# SparkFun_GPS_ZED-F9K.net
KiCad netlist of a schematic drawn in EAGLE
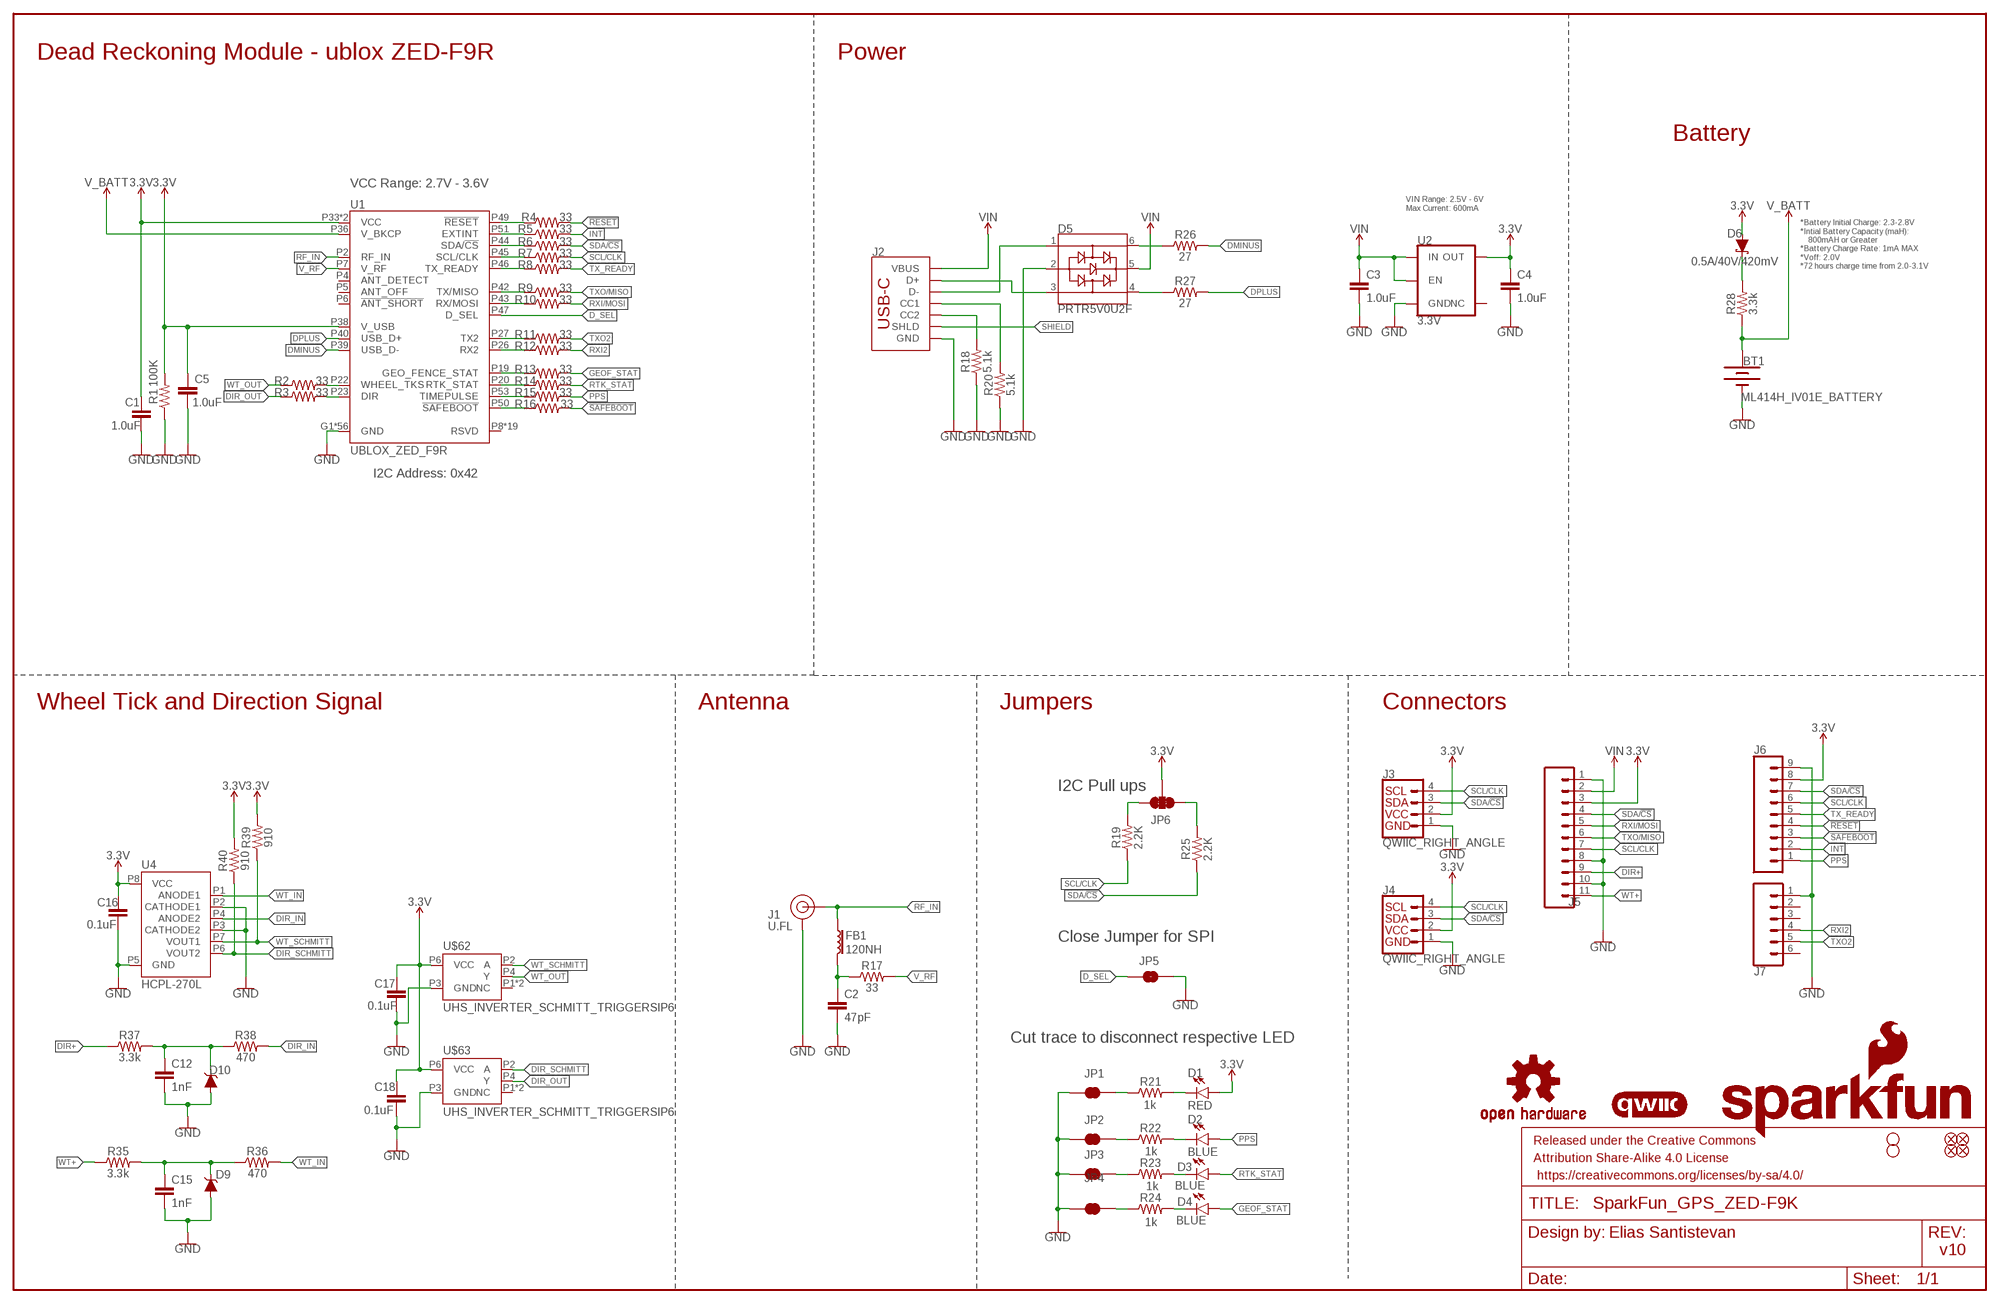
[diagram p0: schematic, sheet 1]

(export (version "E")
  (design (tool "Eeschema 10.0.6"))
  (components
    (comp (ref "$1_36_$_2020-02-13_17-32-45")
      (value "STAND-OFFTIGHT")
      (footprint "eagle-import:STAND-OFF-TIGHT")
      (libsource (lib "eagle-import") (part "STAND-OFFTIGHT"))
    )
    (comp (ref "BT1")
      (value "ML414H_IV01E_BATTERY")
      (footprint "eagle-import:ML414H_IV01E")
      (libsource (lib "eagle-import") (part "ML414H_IV01E_BATTERY"))
    )
    (comp (ref "C1")
      (value "1.0uF")
      (footprint "eagle-import:0603")
      (libsource (lib "eagle-import") (part "1.0UF-0603-16V-10%-X7R"))
    )
    (comp (ref "C2")
      (value "47pF")
      (footprint "eagle-import:0402")
      (libsource (lib "eagle-import") (part "47PF-0402-25V-5%-X7R"))
    )
    (comp (ref "C3")
      (value "1.0uF")
      (footprint "eagle-import:0603")
      (libsource (lib "eagle-import") (part "1.0UF-0603-16V-10%-X7R"))
    )
    (comp (ref "C4")
      (value "1.0uF")
      (footprint "eagle-import:0603")
      (libsource (lib "eagle-import") (part "1.0UF-0603-16V-10%-X7R"))
    )
    (comp (ref "C5")
      (value "1.0uF")
      (footprint "eagle-import:0603")
      (libsource (lib "eagle-import") (part "1.0UF-0603-16V-10%-X7R"))
    )
    (comp (ref "C12")
      (value "1nF")
      (footprint "eagle-import:0402")
      (libsource (lib "eagle-import") (part "1.0NF/1000PF-0402-25V-10%-X7R"))
    )
    (comp (ref "C15")
      (value "1nF")
      (footprint "eagle-import:0402")
      (libsource (lib "eagle-import") (part "1.0NF/1000PF-0402-25V-10%-X7R"))
    )
    (comp (ref "C16")
      (value "0.1uF")
      (footprint "eagle-import:0402")
      (libsource (lib "eagle-import") (part "0.1UF-0402-6.3V-10%-X7R"))
    )
    (comp (ref "C17")
      (value "0.1uF")
      (footprint "eagle-import:0402")
      (libsource (lib "eagle-import") (part "0.1UF-0402-6.3V-10%-X7R"))
    )
    (comp (ref "C18")
      (value "0.1uF")
      (footprint "eagle-import:0402")
      (libsource (lib "eagle-import") (part "0.1UF-0402-6.3V-10%-X7R"))
    )
    (comp (ref "D1")
      (value "RED")
      (footprint "eagle-import:LED-0603")
      (libsource (lib "eagle-import") (part "LED-RED0603"))
    )
    (comp (ref "D2")
      (value "BLUE")
      (footprint "eagle-import:LED-0603")
      (libsource (lib "eagle-import") (part "LED-BLUE0603"))
    )
    (comp (ref "D3")
      (value "BLUE")
      (footprint "eagle-import:LED-0603")
      (libsource (lib "eagle-import") (part "LED-BLUE0603"))
    )
    (comp (ref "D4")
      (value "BLUE")
      (footprint "eagle-import:LED-0603")
      (libsource (lib "eagle-import") (part "LED-BLUE0603"))
    )
    (comp (ref "D5")
      (value "PRTR5V0U2F")
      (footprint "eagle-import:SOT886")
      (libsource (lib "eagle-import") (part "PRTR5V0U2F"))
    )
    (comp (ref "D6")
      (value "0.5A/40V/420mV")
      (footprint "eagle-import:SOD-323")
      (libsource (lib "eagle-import") (part "DIODE-SCHOTTKY-PMEG4005EJ"))
    )
    (comp (ref "D9")
      (value "0.5A/40V/420mV")
      (footprint "eagle-import:SOT23_BZX")
      (libsource (lib "eagle-import") (part "BZX84_DIODE"))
    )
    (comp (ref "D10")
      (value "0.5A/40V/420mV")
      (footprint "eagle-import:SOT23_BZX")
      (libsource (lib "eagle-import") (part "BZX84_DIODE"))
    )
    (comp (ref "FB1")
      (value "120NH")
      (footprint "eagle-import:0402_MURATA")
      (libsource (lib "eagle-import") (part "FERRITE_BEAD_GNSS"))
    )
    (comp (ref "FD1")
      (value "FIDUCIALUFIDUCIAL")
      (footprint "eagle-import:FIDUCIAL-MICRO")
      (libsource (lib "eagle-import") (part "FIDUCIALUFIDUCIAL"))
    )
    (comp (ref "FD2")
      (value "FIDUCIALUFIDUCIAL")
      (footprint "eagle-import:FIDUCIAL-MICRO")
      (libsource (lib "eagle-import") (part "FIDUCIALUFIDUCIAL"))
    )
    (comp (ref "FD3")
      (value "FIDUCIALUFIDUCIAL")
      (footprint "eagle-import:FIDUCIAL-MICRO")
      (libsource (lib "eagle-import") (part "FIDUCIALUFIDUCIAL"))
    )
    (comp (ref "FD4")
      (value "FIDUCIALUFIDUCIAL")
      (footprint "eagle-import:FIDUCIAL-MICRO")
      (libsource (lib "eagle-import") (part "FIDUCIALUFIDUCIAL"))
    )
    (comp (ref "FRAME1")
      (value "FRAME-LEDGER")
      (footprint "eagle-import:CREATIVE_COMMONS")
      (libsource (lib "eagle-import") (part "FRAME-LEDGER"))
    )
    (comp (ref "H2")
      (value "STAND-OFFTIGHT")
      (footprint "eagle-import:STAND-OFF-TIGHT")
      (libsource (lib "eagle-import") (part "STAND-OFFTIGHT"))
    )
    (comp (ref "J1")
      (value "U.FL")
      (footprint "eagle-import:U.FL")
      (libsource (lib "eagle-import") (part "U.FL2PIN"))
    )
    (comp (ref "J2")
      (value "USB_C_2-LAYER_PADS")
      (footprint "eagle-import:USB-C-16P-2LAYER-PADS")
      (libsource (lib "eagle-import") (part "USB_C_2-LAYER_PADS"))
    )
    (comp (ref "J3")
      (value "QWIIC_RIGHT_ANGLE")
      (footprint "eagle-import:JST04_1MM_RA")
      (libsource (lib "eagle-import") (part "QWIIC_CONNECTORJS-1MM"))
    )
    (comp (ref "J4")
      (value "QWIIC_RIGHT_ANGLE")
      (footprint "eagle-import:JST04_1MM_RA")
      (libsource (lib "eagle-import") (part "QWIIC_CONNECTORJS-1MM"))
    )
    (comp (ref "J5")
      (value "CONN_111X11_NO_SILK")
      (footprint "eagle-import:1X11_NO_SILK")
      (libsource (lib "eagle-import") (part "CONN_111X11_NO_SILK"))
    )
    (comp (ref "J6")
      (value "CONN_09NO_SILK")
      (footprint "eagle-import:1X09_NO_SILK")
      (libsource (lib "eagle-import") (part "CONN_09NO_SILK"))
    )
    (comp (ref "J7")
      (value "CONN_06NO_SILK_NO_POP")
      (footprint "eagle-import:1X06_NO_SILK")
      (libsource (lib "eagle-import") (part "CONN_06NO_SILK_NO_POP"))
    )
    (comp (ref "JP1")
      (value "JUMPER-SMT_2_NC_TRACE_SILK")
      (footprint "eagle-import:SMT-JUMPER_2_NC_TRACE_SILK")
      (libsource (lib "eagle-import") (part "JUMPER-SMT_2_NC_TRACE_SILK"))
    )
    (comp (ref "JP2")
      (value "JUMPER-SMT_2_NC_TRACE_SILK")
      (footprint "eagle-import:SMT-JUMPER_2_NC_TRACE_SILK")
      (libsource (lib "eagle-import") (part "JUMPER-SMT_2_NC_TRACE_SILK"))
    )
    (comp (ref "JP3")
      (value "JUMPER-SMT_2_NC_TRACE_SILK")
      (footprint "eagle-import:SMT-JUMPER_2_NC_TRACE_SILK")
      (libsource (lib "eagle-import") (part "JUMPER-SMT_2_NC_TRACE_SILK"))
    )
    (comp (ref "JP4")
      (value "JUMPER-SMT_2_NC_TRACE_SILK")
      (footprint "eagle-import:SMT-JUMPER_2_NC_TRACE_SILK")
      (libsource (lib "eagle-import") (part "JUMPER-SMT_2_NC_TRACE_SILK"))
    )
    (comp (ref "JP5")
      (value "JUMPER-SMT_2_NO_SILK")
      (footprint "eagle-import:SMT-JUMPER_2_NO_SILK")
      (libsource (lib "eagle-import") (part "JUMPER-SMT_2_NO_SILK"))
    )
    (comp (ref "JP6")
      (value "JUMPER-SMT_3_2-NC_TRACE_SILK")
      (footprint "eagle-import:SMT-JUMPER_3_2-NC_TRACE_SILK")
      (libsource (lib "eagle-import") (part "JUMPER-SMT_3_2-NC_TRACE_SILK"))
    )
    (comp (ref "LOGO1")
      (value "OSHW-LOGOM")
      (footprint "eagle-import:OSHW-LOGO-M")
      (libsource (lib "eagle-import") (part "OSHW-LOGOM"))
    )
    (comp (ref "LOGO2")
      (value "QWIIC_LOGO_4MM")
      (footprint "eagle-import:QWIIC_4MM")
      (libsource (lib "eagle-import") (part "QWIIC_LOGO_4MM"))
    )
    (comp (ref "LOGO3")
      (value "SFE_LOGO_NAME_FLAME.2_INCH")
      (footprint "eagle-import:SFE_LOGO_NAME_FLAME_.2")
      (libsource (lib "eagle-import") (part "SFE_LOGO_NAME_FLAME.2_INCH"))
    )
    (comp (ref "R1")
      (value "100K")
      (footprint "eagle-import:0402")
      (libsource (lib "eagle-import") (part "100KOHM-0402-1/16W-1%"))
    )
    (comp (ref "R2")
      (value "33")
      (footprint "eagle-import:0402")
      (libsource (lib "eagle-import") (part "33OHM-0402-1/10W-1%"))
    )
    (comp (ref "R3")
      (value "33")
      (footprint "eagle-import:0402")
      (libsource (lib "eagle-import") (part "33OHM-0402-1/10W-1%"))
    )
    (comp (ref "R4")
      (value "33")
      (footprint "eagle-import:0402")
      (libsource (lib "eagle-import") (part "33OHM-0402-1/10W-1%"))
    )
    (comp (ref "R5")
      (value "33")
      (footprint "eagle-import:0402")
      (libsource (lib "eagle-import") (part "33OHM-0402-1/10W-1%"))
    )
    (comp (ref "R6")
      (value "33")
      (footprint "eagle-import:0402")
      (libsource (lib "eagle-import") (part "33OHM-0402-1/10W-1%"))
    )
    (comp (ref "R7")
      (value "33")
      (footprint "eagle-import:0402")
      (libsource (lib "eagle-import") (part "33OHM-0402-1/10W-1%"))
    )
    (comp (ref "R8")
      (value "33")
      (footprint "eagle-import:0402")
      (libsource (lib "eagle-import") (part "33OHM-0402-1/10W-1%"))
    )
    (comp (ref "R9")
      (value "33")
      (footprint "eagle-import:0402")
      (libsource (lib "eagle-import") (part "33OHM-0402-1/10W-1%"))
    )
    (comp (ref "R10")
      (value "33")
      (footprint "eagle-import:0402")
      (libsource (lib "eagle-import") (part "33OHM-0402-1/10W-1%"))
    )
    (comp (ref "R11")
      (value "33")
      (footprint "eagle-import:0402")
      (libsource (lib "eagle-import") (part "33OHM-0402-1/10W-1%"))
    )
    (comp (ref "R12")
      (value "33")
      (footprint "eagle-import:0402")
      (libsource (lib "eagle-import") (part "33OHM-0402-1/10W-1%"))
    )
    (comp (ref "R13")
      (value "33")
      (footprint "eagle-import:0402")
      (libsource (lib "eagle-import") (part "33OHM-0402-1/10W-1%"))
    )
    (comp (ref "R14")
      (value "33")
      (footprint "eagle-import:0402")
      (libsource (lib "eagle-import") (part "33OHM-0402-1/10W-1%"))
    )
    (comp (ref "R15")
      (value "33")
      (footprint "eagle-import:0402")
      (libsource (lib "eagle-import") (part "33OHM-0402-1/10W-1%"))
    )
    (comp (ref "R16")
      (value "33")
      (footprint "eagle-import:0402")
      (libsource (lib "eagle-import") (part "33OHM-0402-1/10W-1%"))
    )
    (comp (ref "R17")
      (value "33")
      (footprint "eagle-import:0603")
      (libsource (lib "eagle-import") (part "33OHM-0603-1/10W-1%"))
    )
    (comp (ref "R18")
      (value "5.1k")
      (footprint "eagle-import:0402")
      (libsource (lib "eagle-import") (part "5.1KOHM-0402-1/16W-1%"))
    )
    (comp (ref "R19")
      (value "2.2K")
      (footprint "eagle-import:0402")
      (libsource (lib "eagle-import") (part "2.2KOHM-0402-1/16W-1%"))
    )
    (comp (ref "R20")
      (value "5.1k")
      (footprint "eagle-import:0402")
      (libsource (lib "eagle-import") (part "5.1KOHM-0402-1/16W-1%"))
    )
    (comp (ref "R21")
      (value "1KOHM-0402-1/16W-1%")
      (footprint "eagle-import:0402")
      (libsource (lib "eagle-import") (part "1KOHM-0402-1/16W-1%"))
    )
    (comp (ref "R22")
      (value "1KOHM-0402-1/16W-1%")
      (footprint "eagle-import:0402")
      (libsource (lib "eagle-import") (part "1KOHM-0402-1/16W-1%"))
    )
    (comp (ref "R23")
      (value "1KOHM-0402-1/16W-1%")
      (footprint "eagle-import:0402")
      (libsource (lib "eagle-import") (part "1KOHM-0402-1/16W-1%"))
    )
    (comp (ref "R24")
      (value "1KOHM-0402-1/16W-1%")
      (footprint "eagle-import:0402")
      (libsource (lib "eagle-import") (part "1KOHM-0402-1/16W-1%"))
    )
    (comp (ref "R25")
      (value "2.2K")
      (footprint "eagle-import:0402")
      (libsource (lib "eagle-import") (part "2.2KOHM-0402-1/16W-1%"))
    )
    (comp (ref "R26")
      (value "27")
      (footprint "eagle-import:0603")
      (libsource (lib "eagle-import") (part "27OHM-0603-1/10W-1%"))
    )
    (comp (ref "R27")
      (value "27")
      (footprint "eagle-import:0603")
      (libsource (lib "eagle-import") (part "27OHM-0603-1/10W-1%"))
    )
    (comp (ref "R28")
      (value "3.3k")
      (footprint "eagle-import:0603")
      (libsource (lib "eagle-import") (part "3.3KOHM-0603-1/10W-1%"))
    )
    (comp (ref "R35")
      (value "3.3k")
      (footprint "eagle-import:0603")
      (libsource (lib "eagle-import") (part "3.3KOHM-0603-1/10W-1%"))
    )
    (comp (ref "R36")
      (value "470")
      (footprint "eagle-import:0603")
      (libsource (lib "eagle-import") (part "470OHM-0603-1/10W-1%"))
    )
    (comp (ref "R37")
      (value "3.3k")
      (footprint "eagle-import:0603")
      (libsource (lib "eagle-import") (part "3.3KOHM-0603-1/10W-1%"))
    )
    (comp (ref "R38")
      (value "470")
      (footprint "eagle-import:0603")
      (libsource (lib "eagle-import") (part "470OHM-0603-1/10W-1%"))
    )
    (comp (ref "R39")
      (value "910")
      (footprint "eagle-import:0603")
      (libsource (lib "eagle-import") (part "910OHM-0603-1/10W-5%"))
    )
    (comp (ref "R40")
      (value "910")
      (footprint "eagle-import:0603")
      (libsource (lib "eagle-import") (part "910OHM-0603-1/10W-5%"))
    )
    (comp (ref "U$62")
      (value "UHS_INVERTER_SCHMITT_TRIGGERSIP6")
      (footprint "eagle-import:SIP6")
      (libsource (lib "eagle-import") (part "UHS_INVERTER_SCHMITT_TRIGGERSIP6"))
    )
    (comp (ref "U$63")
      (value "UHS_INVERTER_SCHMITT_TRIGGERSIP6")
      (footprint "eagle-import:SIP6")
      (libsource (lib "eagle-import") (part "UHS_INVERTER_SCHMITT_TRIGGERSIP6"))
    )
    (comp (ref "U1")
      (value "UBLOX_ZED_F9R")
      (footprint "eagle-import:UBLOX_ZED_F9R")
      (libsource (lib "eagle-import") (part "UBLOX_ZED_F9R"))
    )
    (comp (ref "U2")
      (value "3.3V")
      (footprint "eagle-import:SOT23-5")
      (libsource (lib "eagle-import") (part "V_REG_AP2112K-3.3V"))
    )
    (comp (ref "U4")
      (value "HCPL-270L")
      (footprint "eagle-import:SOP_8-PIN")
      (libsource (lib "eagle-import") (part "HCPL-270L"))
    )
  )
  (nets
    (net (code "1") (name "/SDA{slash}~{CS}") (class "Default")
      (node (ref "J3") (pin "3") (pinfunction "3_3") (pintype "passive"))
      (node (ref "J4") (pin "3") (pinfunction "3_3") (pintype "passive"))
      (node (ref "J5") (pin "4") (pinfunction "4_4") (pintype "passive"))
      (node (ref "J6") (pin "7") (pinfunction "7_7") (pintype "passive"))
      (node (ref "R25") (pin "1") (pinfunction "1_1") (pintype "passive"))
      (node (ref "R6") (pin "2") (pinfunction "2_2") (pintype "passive"))
    )
    (net (code "2") (name "/~{RESET}") (class "Default")
      (node (ref "J6") (pin "4") (pinfunction "4_4") (pintype "passive"))
      (node (ref "R4") (pin "2") (pinfunction "2_2") (pintype "passive"))
    )
    (net (code "3") (name "/~{SAFEBOOT}") (class "Default")
      (node (ref "J6") (pin "3") (pinfunction "3_3") (pintype "passive"))
      (node (ref "R16") (pin "2") (pinfunction "2_2") (pintype "passive"))
    )
    (net (code "4") (name "3.3V") (class "Default")
      (node (ref "C1") (pin "1") (pinfunction "1_1") (pintype "passive"))
      (node (ref "C16") (pin "1") (pinfunction "1_1") (pintype "passive"))
      (node (ref "C17") (pin "1") (pinfunction "1_1") (pintype "passive"))
      (node (ref "C18") (pin "1") (pinfunction "1_1") (pintype "passive"))
      (node (ref "C4") (pin "1") (pinfunction "1_1") (pintype "passive"))
      (node (ref "C5") (pin "1") (pinfunction "1_1") (pintype "passive"))
      (node (ref "D1") (pin "A") (pinfunction "A_A") (pintype "passive"))
      (node (ref "D6") (pin "A") (pinfunction "A_A") (pintype "passive"))
      (node (ref "J3") (pin "2") (pinfunction "2_2") (pintype "power_in"))
      (node (ref "J4") (pin "2") (pinfunction "2_2") (pintype "power_in"))
      (node (ref "J5") (pin "3") (pinfunction "3_3") (pintype "passive"))
      (node (ref "J6") (pin "8") (pinfunction "8_8") (pintype "passive"))
      (node (ref "JP6") (pin "2") (pinfunction "2_2") (pintype "passive"))
      (node (ref "R1") (pin "2") (pinfunction "2_2") (pintype "passive"))
      (node (ref "R39") (pin "2") (pinfunction "2_2") (pintype "passive"))
      (node (ref "R40") (pin "2") (pinfunction "2_2") (pintype "passive"))
      (node (ref "U$62") (pin "P6") (pinfunction "VCC_P6") (pintype "power_in"))
      (node (ref "U$63") (pin "P6") (pinfunction "VCC_P6") (pintype "power_in"))
      (node (ref "U1") (pin "P33") (pinfunction "VCC_P33") (pintype "power_in"))
      (node (ref "U1") (pin "P34") (pinfunction "VCC_P34") (pintype "power_in"))
      (node (ref "U1") (pin "P38") (pinfunction "V_USB_P38") (pintype "power_in"))
      (node (ref "U2") (pin "5") (pinfunction "OUT_5") (pintype "passive"))
      (node (ref "U4") (pin "P8") (pinfunction "VCC_P8") (pintype "power_in"))
    )
    (net (code "5") (name "DIR+") (class "Default")
      (node (ref "J5") (pin "9") (pinfunction "9_9") (pintype "passive"))
      (node (ref "R37") (pin "1") (pinfunction "1_1") (pintype "passive"))
    )
    (net (code "6") (name "DIR_IN") (class "Default")
      (node (ref "R38") (pin "2") (pinfunction "2_2") (pintype "passive"))
      (node (ref "U4") (pin "P4") (pinfunction "ANODE2_P4") (pintype "input"))
    )
    (net (code "7") (name "DIR_OUT") (class "Default")
      (node (ref "R3") (pin "1") (pinfunction "1_1") (pintype "passive"))
      (node (ref "U$63") (pin "P4") (pinfunction "Y_P4") (pintype "bidirectional"))
    )
    (net (code "8") (name "DIR_SCHMITT") (class "Default")
      (node (ref "R40") (pin "1") (pinfunction "1_1") (pintype "passive"))
      (node (ref "U$63") (pin "P2") (pinfunction "A_P2") (pintype "bidirectional"))
      (node (ref "U4") (pin "P6") (pinfunction "VOUT2_P6") (pintype "output"))
    )
    (net (code "9") (name "DMINUS") (class "Default")
      (node (ref "R26") (pin "2") (pinfunction "2_2") (pintype "passive"))
      (node (ref "U1") (pin "P39") (pinfunction "USB_D-_P39") (pintype "bidirectional"))
    )
    (net (code "10") (name "DPLUS") (class "Default")
      (node (ref "R27") (pin "2") (pinfunction "2_2") (pintype "passive"))
      (node (ref "U1") (pin "P40") (pinfunction "USB_D+_P40") (pintype "bidirectional"))
    )
    (net (code "11") (name "D_SEL") (class "Default")
      (node (ref "JP5") (pin "1") (pinfunction "1_1") (pintype "passive"))
      (node (ref "U1") (pin "P47") (pinfunction "D_SEL_P47") (pintype "bidirectional"))
    )
    (net (code "12") (name "GEOF_STAT") (class "Default")
      (node (ref "D4") (pin "A") (pinfunction "A_A") (pintype "passive"))
      (node (ref "R13") (pin "2") (pinfunction "2_2") (pintype "passive"))
    )
    (net (code "13") (name "GND") (class "Default")
      (node (ref "BT1") (pin "-") (pinfunction "-_-") (pintype "power_in"))
      (node (ref "C1") (pin "2") (pinfunction "2_2") (pintype "passive"))
      (node (ref "C12") (pin "2") (pinfunction "2_2") (pintype "passive"))
      (node (ref "C15") (pin "2") (pinfunction "2_2") (pintype "passive"))
      (node (ref "C16") (pin "2") (pinfunction "2_2") (pintype "passive"))
      (node (ref "C17") (pin "2") (pinfunction "2_2") (pintype "passive"))
      (node (ref "C18") (pin "2") (pinfunction "2_2") (pintype "passive"))
      (node (ref "C2") (pin "2") (pinfunction "2_2") (pintype "passive"))
      (node (ref "C3") (pin "2") (pinfunction "2_2") (pintype "passive"))
      (node (ref "C4") (pin "2") (pinfunction "2_2") (pintype "passive"))
      (node (ref "C5") (pin "2") (pinfunction "2_2") (pintype "passive"))
      (node (ref "D10") (pin "P1") (pinfunction "A_P1") (pintype "passive"))
      (node (ref "D5") (pin "2") (pinfunction "2_2") (pintype "bidirectional"))
      (node (ref "D9") (pin "P1") (pinfunction "A_P1") (pintype "passive"))
      (node (ref "J1") (pin "1") (pinfunction "GND_1") (pintype "bidirectional"))
      (node (ref "J1") (pin "2") (pinfunction "GND_2") (pintype "bidirectional"))
      (node (ref "J2") (pin "GND") (pinfunction "GND_GND") (pintype "bidirectional"))
      (node (ref "J2") (pin "GND2") (pinfunction "GND_GND2") (pintype "bidirectional"))
      (node (ref "J3") (pin "1") (pinfunction "1_1") (pintype "power_in"))
      (node (ref "J4") (pin "1") (pinfunction "1_1") (pintype "power_in"))
      (node (ref "J5") (pin "1") (pinfunction "1_1") (pintype "passive"))
      (node (ref "J5") (pin "10") (pinfunction "10_10") (pintype "passive"))
      (node (ref "J5") (pin "8") (pinfunction "8_8") (pintype "passive"))
      (node (ref "J6") (pin "9") (pinfunction "9_9") (pintype "passive"))
      (node (ref "J7") (pin "1") (pinfunction "1_1") (pintype "passive"))
      (node (ref "JP1") (pin "1") (pinfunction "1_1") (pintype "passive"))
      (node (ref "JP2") (pin "1") (pinfunction "1_1") (pintype "passive"))
      (node (ref "JP3") (pin "1") (pinfunction "1_1") (pintype "passive"))
      (node (ref "JP4") (pin "1") (pinfunction "1_1") (pintype "passive"))
      (node (ref "JP5") (pin "2") (pinfunction "2_2") (pintype "passive"))
      (node (ref "R1") (pin "1") (pinfunction "1_1") (pintype "passive"))
      (node (ref "R18") (pin "1") (pinfunction "1_1") (pintype "passive"))
      (node (ref "R20") (pin "1") (pinfunction "1_1") (pintype "passive"))
      (node (ref "U$62") (pin "P3") (pinfunction "GND_P3") (pintype "power_in"))
      (node (ref "U$63") (pin "P3") (pinfunction "GND_P3") (pintype "power_in"))
      (node (ref "U1") (pin "G1") (pinfunction "GND_G1") (pintype "power_in"))
      (node (ref "U1") (pin "G10") (pinfunction "GND_G10") (pintype "power_in"))
      (node (ref "U1") (pin "G11") (pinfunction "GND_G11") (pintype "power_in"))
      (node (ref "U1") (pin "G12") (pinfunction "GND_G12") (pintype "power_in"))
      (node (ref "U1") (pin "G13") (pinfunction "GND_G13") (pintype "power_in"))
      (node (ref "U1") (pin "G14") (pinfunction "GND_G14") (pintype "power_in"))
      (node (ref "U1") (pin "G15") (pinfunction "GND_G15") (pintype "power_in"))
      (node (ref "U1") (pin "G16") (pinfunction "GND_G16") (pintype "power_in"))
      (node (ref "U1") (pin "G17") (pinfunction "GND_G17") (pintype "power_in"))
      (node (ref "U1") (pin "G18") (pinfunction "GND_G18") (pintype "power_in"))
      (node (ref "U1") (pin "G19") (pinfunction "GND_G19") (pintype "power_in"))
      (node (ref "U1") (pin "G2") (pinfunction "GND_G2") (pintype "power_in"))
      (node (ref "U1") (pin "G20") (pinfunction "GND_G20") (pintype "power_in"))
      (node (ref "U1") (pin "G21") (pinfunction "GND_G21") (pintype "power_in"))
      (node (ref "U1") (pin "G22") (pinfunction "GND_G22") (pintype "power_in"))
      (node (ref "U1") (pin "G23") (pinfunction "GND_G23") (pintype "power_in"))
      (node (ref "U1") (pin "G24") (pinfunction "GND_G24") (pintype "power_in"))
      (node (ref "U1") (pin "G25") (pinfunction "GND_G25") (pintype "power_in"))
      (node (ref "U1") (pin "G26") (pinfunction "GND_G26") (pintype "power_in"))
      (node (ref "U1") (pin "G27") (pinfunction "GND_G27") (pintype "power_in"))
      (node (ref "U1") (pin "G28") (pinfunction "GND_G28") (pintype "power_in"))
      (node (ref "U1") (pin "G29") (pinfunction "GND_G29") (pintype "power_in"))
      (node (ref "U1") (pin "G3") (pinfunction "GND_G3") (pintype "power_in"))
      (node (ref "U1") (pin "G30") (pinfunction "GND_G30") (pintype "power_in"))
      (node (ref "U1") (pin "G31") (pinfunction "GND_G31") (pintype "power_in"))
      (node (ref "U1") (pin "G32") (pinfunction "GND_G32") (pintype "power_in"))
      (node (ref "U1") (pin "G33") (pinfunction "GND_G33") (pintype "power_in"))
      (node (ref "U1") (pin "G34") (pinfunction "GND_G34") (pintype "power_in"))
      (node (ref "U1") (pin "G35") (pinfunction "GND_G35") (pintype "power_in"))
      (node (ref "U1") (pin "G36") (pinfunction "GND_G36") (pintype "power_in"))
      (node (ref "U1") (pin "G37") (pinfunction "GND_G37") (pintype "power_in"))
      (node (ref "U1") (pin "G38") (pinfunction "GND_G38") (pintype "power_in"))
      (node (ref "U1") (pin "G39") (pinfunction "GND_G39") (pintype "power_in"))
      (node (ref "U1") (pin "G4") (pinfunction "GND_G4") (pintype "power_in"))
      (node (ref "U1") (pin "G40") (pinfunction "GND_G40") (pintype "power_in"))
      (node (ref "U1") (pin "G41") (pinfunction "GND_G41") (pintype "power_in"))
      (node (ref "U1") (pin "G42") (pinfunction "GND_G42") (pintype "power_in"))
      (node (ref "U1") (pin "G43") (pinfunction "GND_G43") (pintype "power_in"))
      (node (ref "U1") (pin "G44") (pinfunction "GND_G44") (pintype "power_in"))
      (node (ref "U1") (pin "G45") (pinfunction "GND_G45") (pintype "power_in"))
      (node (ref "U1") (pin "G46") (pinfunction "GND_G46") (pintype "power_in"))
      (node (ref "U1") (pin "G47") (pinfunction "GND_G47") (pintype "power_in"))
      (node (ref "U1") (pin "G48") (pinfunction "GND_G48") (pintype "power_in"))
      (node (ref "U1") (pin "G5") (pinfunction "GND_G5") (pintype "power_in"))
      (node (ref "U1") (pin "G6") (pinfunction "GND_G6") (pintype "power_in"))
      (node (ref "U1") (pin "G7") (pinfunction "GND_G7") (pintype "power_in"))
      (node (ref "U1") (pin "G8") (pinfunction "GND_G8") (pintype "power_in"))
      (node (ref "U1") (pin "G9") (pinfunction "GND_G9") (pintype "power_in"))
      (node (ref "U1") (pin "P1") (pinfunction "GND_P1") (pintype "power_in"))
      (node (ref "U1") (pin "P12") (pinfunction "GND_P12") (pintype "power_in"))
      (node (ref "U1") (pin "P14") (pinfunction "GND_P14") (pintype "power_in"))
      (node (ref "U1") (pin "P3") (pinfunction "GND_P3") (pintype "power_in"))
      (node (ref "U1") (pin "P32") (pinfunction "GND_P32") (pintype "power_in"))
      (node (ref "U1") (pin "P37") (pinfunction "GND_P37") (pintype "power_in"))
      (node (ref "U1") (pin "P41") (pinfunction "GND_P41") (pintype "power_in"))
      (node (ref "U1") (pin "P48") (pinfunction "GND_P48") (pintype "power_in"))
      (node (ref "U2") (pin "2") (pinfunction "GND_2") (pintype "input"))
      (node (ref "U4") (pin "P2") (pinfunction "CATHODE1_P2") (pintype "input"))
      (node (ref "U4") (pin "P3") (pinfunction "CATHODE2_P3") (pintype "input"))
      (node (ref "U4") (pin "P5") (pinfunction "GND_P5") (pintype "power_in"))
    )
    (net (code "14") (name "INT") (class "Default")
      (node (ref "J6") (pin "2") (pinfunction "2_2") (pintype "passive"))
      (node (ref "R5") (pin "2") (pinfunction "2_2") (pintype "passive"))
    )
    (net (code "15") (name "Net-(D1-PadC)") (class "Default")
      (node (ref "D1") (pin "C") (pinfunction "C_C") (pintype "passive"))
      (node (ref "R21") (pin "2") (pinfunction "2_2") (pintype "passive"))
    )
    (net (code "16") (name "Net-(D2-PadC)") (class "Default")
      (node (ref "D2") (pin "C") (pinfunction "C_C") (pintype "passive"))
      (node (ref "R22") (pin "2") (pinfunction "2_2") (pintype "passive"))
    )
    (net (code "17") (name "Net-(D3-PadC)") (class "Default")
      (node (ref "D3") (pin "C") (pinfunction "C_C") (pintype "passive"))
      (node (ref "R23") (pin "2") (pinfunction "2_2") (pintype "passive"))
    )
    (net (code "18") (name "Net-(D4-PadC)") (class "Default")
      (node (ref "D4") (pin "C") (pinfunction "C_C") (pintype "passive"))
      (node (ref "R24") (pin "2") (pinfunction "2_2") (pintype "passive"))
    )
    (net (code "19") (name "Net-(D5-Pad1)") (class "Default")
      (node (ref "D5") (pin "1") (pinfunction "1_1") (pintype "bidirectional"))
      (node (ref "J2") (pin "A7") (pinfunction "D-_A7") (pintype "bidirectional"))
      (node (ref "J2") (pin "B7") (pinfunction "D-_B7") (pintype "bidirectional"))
    )
    (net (code "20") (name "Net-(D5-Pad3)") (class "Default")
      (node (ref "D5") (pin "3") (pinfunction "3_3") (pintype "bidirectional"))
      (node (ref "J2") (pin "A6") (pinfunction "D+_A6") (pintype "bidirectional"))
      (node (ref "J2") (pin "B6") (pinfunction "D+_B6") (pintype "bidirectional"))
    )
    (net (code "21") (name "Net-(D5-Pad4)") (class "Default")
      (node (ref "D5") (pin "4") (pinfunction "4_4") (pintype "bidirectional"))
      (node (ref "R27") (pin "1") (pinfunction "1_1") (pintype "passive"))
    )
    (net (code "22") (name "Net-(D5-Pad6)") (class "Default")
      (node (ref "D5") (pin "6") (pinfunction "6_6") (pintype "bidirectional"))
      (node (ref "R26") (pin "1") (pinfunction "1_1") (pintype "passive"))
    )
    (net (code "23") (name "Net-(D6-PadC)") (class "Default")
      (node (ref "D6") (pin "C") (pinfunction "C_C") (pintype "passive"))
      (node (ref "R28") (pin "2") (pinfunction "2_2") (pintype "passive"))
    )
    (net (code "24") (name "Net-(D9-C)") (class "Default")
      (node (ref "C15") (pin "1") (pinfunction "1_1") (pintype "passive"))
      (node (ref "D9") (pin "P3") (pinfunction "C_P3") (pintype "passive"))
      (node (ref "R35") (pin "2") (pinfunction "2_2") (pintype "passive"))
      (node (ref "R36") (pin "1") (pinfunction "1_1") (pintype "passive"))
    )
    (net (code "25") (name "Net-(D10-C)") (class "Default")
      (node (ref "C12") (pin "1") (pinfunction "1_1") (pintype "passive"))
      (node (ref "D10") (pin "P3") (pinfunction "C_P3") (pintype "passive"))
      (node (ref "R37") (pin "2") (pinfunction "2_2") (pintype "passive"))
      (node (ref "R38") (pin "1") (pinfunction "1_1") (pintype "passive"))
    )
    (net (code "26") (name "Net-(FB1-2)") (class "Default")
      (node (ref "C2") (pin "1") (pinfunction "1_1") (pintype "passive"))
      (node (ref "FB1") (pin "P2") (pinfunction "2_P2") (pintype "passive"))
      (node (ref "R17") (pin "1") (pinfunction "1_1") (pintype "passive"))
    )
    (net (code "27") (name "Net-(J2-CC1)") (class "Default")
      (node (ref "J2") (pin "A5") (pinfunction "CC1_A5") (pintype "bidirectional"))
      (node (ref "R20") (pin "2") (pinfunction "2_2") (pintype "passive"))
    )
    (net (code "28") (name "Net-(J2-CC2)") (class "Default")
      (node (ref "J2") (pin "B5") (pinfunction "CC2_B5") (pintype "bidirectional"))
      (node (ref "R18") (pin "2") (pinfunction "2_2") (pintype "passive"))
    )
    (net (code "29") (name "Net-(JP1-Pad2)") (class "Default")
      (node (ref "JP1") (pin "2") (pinfunction "2_2") (pintype "passive"))
      (node (ref "R21") (pin "1") (pinfunction "1_1") (pintype "passive"))
    )
    (net (code "30") (name "Net-(JP2-Pad2)") (class "Default")
      (node (ref "JP2") (pin "2") (pinfunction "2_2") (pintype "passive"))
      (node (ref "R22") (pin "1") (pinfunction "1_1") (pintype "passive"))
    )
    (net (code "31") (name "Net-(JP3-Pad2)") (class "Default")
      (node (ref "JP3") (pin "2") (pinfunction "2_2") (pintype "passive"))
      (node (ref "R23") (pin "1") (pinfunction "1_1") (pintype "passive"))
    )
    (net (code "32") (name "Net-(JP4-Pad2)") (class "Default")
      (node (ref "JP4") (pin "2") (pinfunction "2_2") (pintype "passive"))
      (node (ref "R24") (pin "1") (pinfunction "1_1") (pintype "passive"))
    )
    (net (code "33") (name "Net-(JP6-Pad1)") (class "Default")
      (node (ref "JP6") (pin "1") (pinfunction "1_1") (pintype "passive"))
      (node (ref "R25") (pin "2") (pinfunction "2_2") (pintype "passive"))
    )
    (net (code "34") (name "Net-(JP6-Pad3)") (class "Default")
      (node (ref "JP6") (pin "3") (pinfunction "3_3") (pintype "passive"))
      (node (ref "R19") (pin "2") (pinfunction "2_2") (pintype "passive"))
    )
    (net (code "35") (name "Net-(U1-DIR)") (class "Default")
      (node (ref "R3") (pin "2") (pinfunction "2_2") (pintype "passive"))
      (node (ref "U1") (pin "P23") (pinfunction "DIR_P23") (pintype "input"))
    )
    (net (code "36") (name "Net-(U1-EXTINT)") (class "Default")
      (node (ref "R5") (pin "1") (pinfunction "1_1") (pintype "passive"))
      (node (ref "U1") (pin "P51") (pinfunction "EXTINT_P51") (pintype "bidirectional"))
    )
    (net (code "37") (name "Net-(U1-GEO_FENCE_STAT)") (class "Default")
      (node (ref "R13") (pin "1") (pinfunction "1_1") (pintype "passive"))
      (node (ref "U1") (pin "P19") (pinfunction "GEO_FENCE_STAT_P19") (pintype "output"))
    )
    (net (code "38") (name "Net-(U1-RTK_STAT)") (class "Default")
      (node (ref "R14") (pin "1") (pinfunction "1_1") (pintype "passive"))
      (node (ref "U1") (pin "P20") (pinfunction "RTK_STAT_P20") (pintype "output"))
    )
    (net (code "39") (name "Net-(U1-RX2)") (class "Default")
      (node (ref "R12") (pin "1") (pinfunction "1_1") (pintype "passive"))
      (node (ref "U1") (pin "P26") (pinfunction "RX2_P26") (pintype "input"))
    )
    (net (code "40") (name "Net-(U1-RX{slash}MOSI)") (class "Default")
      (node (ref "R10") (pin "1") (pinfunction "1_1") (pintype "passive"))
      (node (ref "U1") (pin "P43") (pinfunction "RX/MOSI_P43") (pintype "bidirectional"))
    )
    (net (code "41") (name "Net-(U1-SCL{slash}CLK)") (class "Default")
      (node (ref "R7") (pin "1") (pinfunction "1_1") (pintype "passive"))
      (node (ref "U1") (pin "P45") (pinfunction "SCL/CLK_P45") (pintype "bidirectional"))
    )
    (net (code "42") (name "Net-(U1-SDA{slash}~{CS})") (class "Default")
      (node (ref "R6") (pin "1") (pinfunction "1_1") (pintype "passive"))
      (node (ref "U1") (pin "P44") (pinfunction "SDA/~{CS}_P44") (pintype "bidirectional"))
    )
    (net (code "43") (name "Net-(U1-TIMEPULSE)") (class "Default")
      (node (ref "R15") (pin "1") (pinfunction "1_1") (pintype "passive"))
      (node (ref "U1") (pin "P53") (pinfunction "TIMEPULSE_P53") (pintype "output"))
    )
    (net (code "44") (name "Net-(U1-TX2)") (class "Default")
      (node (ref "R11") (pin "1") (pinfunction "1_1") (pintype "passive"))
      (node (ref "U1") (pin "P27") (pinfunction "TX2_P27") (pintype "output"))
    )
    (net (code "45") (name "Net-(U1-TX_READY)") (class "Default")
      (node (ref "R8") (pin "1") (pinfunction "1_1") (pintype "passive"))
      (node (ref "U1") (pin "P46") (pinfunction "TX_READY_P46") (pintype "bidirectional"))
    )
    (net (code "46") (name "Net-(U1-TX{slash}MISO)") (class "Default")
      (node (ref "R9") (pin "1") (pinfunction "1_1") (pintype "passive"))
      (node (ref "U1") (pin "P42") (pinfunction "TX/MISO_P42") (pintype "bidirectional"))
    )
    (net (code "47") (name "Net-(U1-WHEEL_TKS)") (class "Default")
      (node (ref "R2") (pin "2") (pinfunction "2_2") (pintype "passive"))
      (node (ref "U1") (pin "P22") (pinfunction "WHEEL_TKS_P22") (pintype "input"))
    )
    (net (code "48") (name "Net-(U1-~{RESET})") (class "Default")
      (node (ref "R4") (pin "1") (pinfunction "1_1") (pintype "passive"))
      (node (ref "U1") (pin "P49") (pinfunction "~{RESET}_P49") (pintype "bidirectional"))
    )
    (net (code "49") (name "Net-(U1-~{SAFEBOOT})") (class "Default")
      (node (ref "R16") (pin "1") (pinfunction "1_1") (pintype "passive"))
      (node (ref "U1") (pin "P50") (pinfunction "~{SAFEBOOT}_P50") (pintype "input"))
    )
    (net (code "50") (name "PPS") (class "Default")
      (node (ref "D2") (pin "A") (pinfunction "A_A") (pintype "passive"))
      (node (ref "J6") (pin "1") (pinfunction "1_1") (pintype "passive"))
      (node (ref "R15") (pin "2") (pinfunction "2_2") (pintype "passive"))
    )
    (net (code "51") (name "RF_IN") (class "Default")
      (node (ref "FB1") (pin "P1") (pinfunction "1_P1") (pintype "passive"))
      (node (ref "J1") (pin "FEED") (pinfunction "SIGNAL_FEED") (pintype "bidirectional"))
      (node (ref "U1") (pin "P2") (pinfunction "RF_IN_P2") (pintype "input"))
    )
    (net (code "52") (name "RTK_STAT") (class "Default")
      (node (ref "D3") (pin "A") (pinfunction "A_A") (pintype "passive"))
      (node (ref "R14") (pin "2") (pinfunction "2_2") (pintype "passive"))
    )
    (net (code "53") (name "RXI2") (class "Default")
      (node (ref "J7") (pin "4") (pinfunction "4_4") (pintype "passive"))
      (node (ref "R12") (pin "2") (pinfunction "2_2") (pintype "passive"))
    )
    (net (code "54") (name "RXI{slash}MOSI") (class "Default")
      (node (ref "J5") (pin "5") (pinfunction "5_5") (pintype "passive"))
      (node (ref "R10") (pin "2") (pinfunction "2_2") (pintype "passive"))
    )
    (net (code "55") (name "SCL{slash}CLK") (class "Default")
      (node (ref "J3") (pin "4") (pinfunction "4_4") (pintype "passive"))
      (node (ref "J4") (pin "4") (pinfunction "4_4") (pintype "passive"))
      (node (ref "J5") (pin "7") (pinfunction "7_7") (pintype "passive"))
      (node (ref "J6") (pin "6") (pinfunction "6_6") (pintype "passive"))
      (node (ref "R19") (pin "1") (pinfunction "1_1") (pintype "passive"))
      (node (ref "R7") (pin "2") (pinfunction "2_2") (pintype "passive"))
    )
    (net (code "56") (name "SHIELD") (class "Default")
      (node (ref "J2") (pin "SHLD1") (pinfunction "SHLD_SHLD1") (pintype "bidirectional"))
      (node (ref "J2") (pin "SHLD2") (pinfunction "SHLD_SHLD2") (pintype "bidirectional"))
      (node (ref "J2") (pin "SHLD3") (pinfunction "SHLD_SHLD3") (pintype "bidirectional"))
      (node (ref "J2") (pin "SHLD4") (pinfunction "SHLD_SHLD4") (pintype "bidirectional"))
    )
    (net (code "57") (name "TXO2") (class "Default")
      (node (ref "J7") (pin "5") (pinfunction "5_5") (pintype "passive"))
      (node (ref "R11") (pin "2") (pinfunction "2_2") (pintype "passive"))
    )
    (net (code "58") (name "TXO{slash}MISO") (class "Default")
      (node (ref "J5") (pin "6") (pinfunction "6_6") (pintype "passive"))
      (node (ref "R9") (pin "2") (pinfunction "2_2") (pintype "passive"))
    )
    (net (code "59") (name "TX_READY") (class "Default")
      (node (ref "J6") (pin "5") (pinfunction "5_5") (pintype "passive"))
      (node (ref "R8") (pin "2") (pinfunction "2_2") (pintype "passive"))
    )
    (net (code "60") (name "VIN") (class "Default")
      (node (ref "C3") (pin "1") (pinfunction "1_1") (pintype "passive"))
      (node (ref "D5") (pin "5") (pinfunction "5_5") (pintype "bidirectional"))
      (node (ref "J2") (pin "VBUS1") (pinfunction "VBUS_VBUS1") (pintype "bidirectional"))
      (node (ref "J2") (pin "VBUS2") (pinfunction "VBUS_VBUS2") (pintype "bidirectional"))
      (node (ref "J5") (pin "2") (pinfunction "2_2") (pintype "passive"))
      (node (ref "U2") (pin "1") (pinfunction "IN_1") (pintype "input"))
      (node (ref "U2") (pin "3") (pinfunction "EN_3") (pintype "input"))
    )
    (net (code "61") (name "V_BATT") (class "Default")
      (node (ref "BT1") (pin "+") (pinfunction "+_+") (pintype "power_in"))
      (node (ref "R28") (pin "1") (pinfunction "1_1") (pintype "passive"))
      (node (ref "U1") (pin "P36") (pinfunction "V_BKCP_P36") (pintype "power_in"))
    )
    (net (code "62") (name "V_RF") (class "Default")
      (node (ref "R17") (pin "2") (pinfunction "2_2") (pintype "passive"))
      (node (ref "U1") (pin "P7") (pinfunction "V_RF_P7") (pintype "output"))
    )
    (net (code "63") (name "WT+") (class "Default")
      (node (ref "J5") (pin "11") (pinfunction "11_11") (pintype "passive"))
      (node (ref "R35") (pin "1") (pinfunction "1_1") (pintype "passive"))
    )
    (net (code "64") (name "WT_IN") (class "Default")
      (node (ref "R36") (pin "2") (pinfunction "2_2") (pintype "passive"))
      (node (ref "U4") (pin "P1") (pinfunction "ANODE1_P1") (pintype "input"))
    )
    (net (code "65") (name "WT_OUT") (class "Default")
      (node (ref "R2") (pin "1") (pinfunction "1_1") (pintype "passive"))
      (node (ref "U$62") (pin "P4") (pinfunction "Y_P4") (pintype "bidirectional"))
    )
    (net (code "66") (name "WT_SCHMITT") (class "Default")
      (node (ref "R39") (pin "1") (pinfunction "1_1") (pintype "passive"))
      (node (ref "U$62") (pin "P2") (pinfunction "A_P2") (pintype "bidirectional"))
      (node (ref "U4") (pin "P7") (pinfunction "VOUT1_P7") (pintype "output"))
    )
    (net (code "67") (name "unconnected-(J7-Pad2)") (class "Default")
      (node (ref "J7") (pin "2") (pinfunction "2_2") (pintype "passive"))
    )
    (net (code "68") (name "unconnected-(J7-Pad3)") (class "Default")
      (node (ref "J7") (pin "3") (pinfunction "3_3") (pintype "passive"))
    )
    (net (code "69") (name "unconnected-(J7-Pad6)") (class "Default")
      (node (ref "J7") (pin "6") (pinfunction "6_6") (pintype "passive"))
    )
    (net (code "70") (name "unconnected-(U$62-NC-PadP1)") (class "Default")
      (node (ref "U$62") (pin "P1") (pinfunction "NC_P1") (pintype "no_connect"))
    )
    (net (code "71") (name "unconnected-(U$62-NC-PadP5)") (class "Default")
      (node (ref "U$62") (pin "P5") (pinfunction "NC_P5") (pintype "no_connect"))
    )
    (net (code "72") (name "unconnected-(U$63-NC-PadP1)") (class "Default")
      (node (ref "U$63") (pin "P1") (pinfunction "NC_P1") (pintype "no_connect"))
    )
    (net (code "73") (name "unconnected-(U$63-NC-PadP5)") (class "Default")
      (node (ref "U$63") (pin "P5") (pinfunction "NC_P5") (pintype "no_connect"))
    )
    (net (code "74") (name "unconnected-(U1-ANT_DETECT-PadP4)") (class "Default")
      (node (ref "U1") (pin "P4") (pinfunction "ANT_DETECT_P4") (pintype "input"))
    )
    (net (code "75") (name "unconnected-(U1-ANT_OFF-PadP5)") (class "Default")
      (node (ref "U1") (pin "P5") (pinfunction "ANT_OFF_P5") (pintype "output"))
    )
    (net (code "76") (name "unconnected-(U1-RSVD-PadP8)") (class "Default")
      (node (ref "U1") (pin "P8") (pinfunction "RSVD_P8") (pintype "no_connect"))
    )
    (net (code "77") (name "unconnected-(U1-RSVD-PadP9)") (class "Default")
      (node (ref "U1") (pin "P9") (pinfunction "RSVD_P9") (pintype "no_connect"))
    )
    (net (code "78") (name "unconnected-(U1-RSVD-PadP10)") (class "Default")
      (node (ref "U1") (pin "P10") (pinfunction "RSVD_P10") (pintype "no_connect"))
    )
    (net (code "79") (name "unconnected-(U1-RSVD-PadP11)") (class "Default")
      (node (ref "U1") (pin "P11") (pinfunction "RSVD_P11") (pintype "no_connect"))
    )
    (net (code "80") (name "unconnected-(U1-RSVD-PadP13)") (class "Default")
      (node (ref "U1") (pin "P13") (pinfunction "RSVD_P13") (pintype "no_connect"))
    )
    (net (code "81") (name "unconnected-(U1-RSVD-PadP15)") (class "Default")
      (node (ref "U1") (pin "P15") (pinfunction "RSVD_P15") (pintype "no_connect"))
    )
    (net (code "82") (name "unconnected-(U1-RSVD-PadP16)") (class "Default")
      (node (ref "U1") (pin "P16") (pinfunction "RSVD_P16") (pintype "no_connect"))
    )
    (net (code "83") (name "unconnected-(U1-RSVD-PadP17)") (class "Default")
      (node (ref "U1") (pin "P17") (pinfunction "RSVD_P17") (pintype "no_connect"))
    )
    (net (code "84") (name "unconnected-(U1-RSVD-PadP18)") (class "Default")
      (node (ref "U1") (pin "P18") (pinfunction "RSVD_P18") (pintype "no_connect"))
    )
    (net (code "85") (name "unconnected-(U1-RSVD-PadP21)") (class "Default")
      (node (ref "U1") (pin "P21") (pinfunction "RSVD_P21") (pintype "no_connect"))
    )
    (net (code "86") (name "unconnected-(U1-RSVD-PadP24)") (class "Default")
      (node (ref "U1") (pin "P24") (pinfunction "RSVD_P24") (pintype "no_connect"))
    )
    (net (code "87") (name "unconnected-(U1-RSVD-PadP25)") (class "Default")
      (node (ref "U1") (pin "P25") (pinfunction "RSVD_P25") (pintype "no_connect"))
    )
    (net (code "88") (name "unconnected-(U1-RSVD-PadP28)") (class "Default")
      (node (ref "U1") (pin "P28") (pinfunction "RSVD_P28") (pintype "no_connect"))
    )
    (net (code "89") (name "unconnected-(U1-RSVD-PadP29)") (class "Default")
      (node (ref "U1") (pin "P29") (pinfunction "RSVD_P29") (pintype "no_connect"))
    )
    (net (code "90") (name "unconnected-(U1-RSVD-PadP30)") (class "Default")
      (node (ref "U1") (pin "P30") (pinfunction "RSVD_P30") (pintype "no_connect"))
    )
    (net (code "91") (name "unconnected-(U1-RSVD-PadP31)") (class "Default")
      (node (ref "U1") (pin "P31") (pinfunction "RSVD_P31") (pintype "no_connect"))
    )
    (net (code "92") (name "unconnected-(U1-RSVD-PadP35)") (class "Default")
      (node (ref "U1") (pin "P35") (pinfunction "RSVD_P35") (pintype "no_connect"))
    )
    (net (code "93") (name "unconnected-(U1-RSVD-PadP52)") (class "Default")
      (node (ref "U1") (pin "P52") (pinfunction "RSVD_P52") (pintype "no_connect"))
    )
    (net (code "94") (name "unconnected-(U1-RSVD-PadP54)") (class "Default")
      (node (ref "U1") (pin "P54") (pinfunction "RSVD_P54") (pintype "no_connect"))
    )
    (net (code "95") (name "unconnected-(U1-~{ANT_SHORT}-PadP6)") (class "Default")
      (node (ref "U1") (pin "P6") (pinfunction "~{ANT_SHORT}_P6") (pintype "output"))
    )
    (net (code "96") (name "unconnected-(U2-NC-Pad4)") (class "Default")
      (node (ref "U2") (pin "4") (pinfunction "NC_4") (pintype "no_connect"))
    )
  )
)
